# 2back-1motor.net
KiCad netlist of a schematic drawn in EAGLE
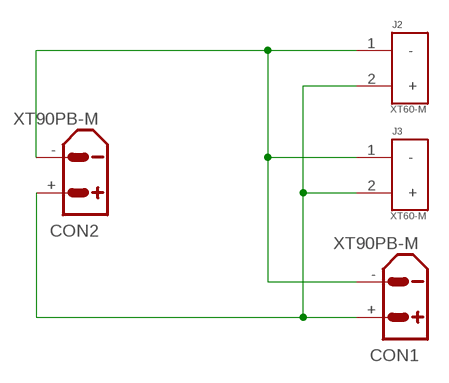
[diagram p0: schematic, sheet 1]

(export (version "E")
  (design (tool "Eeschema 10.0.6"))
  (components
    (comp (ref "CON1")
      (value "XT90PB-M")
      (footprint "eagle-import:XT90PB-M")
      (libsource (lib "eagle-import") (part "XT90PB-M"))
    )
    (comp (ref "CON2")
      (value "XT90PB-M")
      (footprint "eagle-import:XT90PB-M")
      (libsource (lib "eagle-import") (part "XT90PB-M"))
    )
    (comp (ref "J2")
      (value "XT60-M")
      (footprint "eagle-import:AMASS_XT60-M")
      (fields (field (name "MF") "AMASS"))
      (libsource (lib "eagle-import") (part "XT60-M"))
    )
    (comp (ref "J3")
      (value "XT60-M")
      (footprint "eagle-import:AMASS_XT60-M")
      (fields (field (name "MF") "AMASS"))
      (libsource (lib "eagle-import") (part "XT60-M"))
    )
  )
  (nets
    (net (code "1") (name "Net-(J2-+)") (class "Default")
      (node (ref "CON1") (pin "+") (pinfunction "+_+") (pintype "power_in"))
      (node (ref "CON2") (pin "+") (pinfunction "+_+") (pintype "power_in"))
      (node (ref "J2") (pin "2") (pinfunction "+_2") (pintype "passive"))
      (node (ref "J3") (pin "2") (pinfunction "+_2") (pintype "passive"))
    )
    (net (code "2") (name "Net-(J2--)") (class "Default")
      (node (ref "CON1") (pin "-") (pinfunction "-_-") (pintype "power_in"))
      (node (ref "CON2") (pin "-") (pinfunction "-_-") (pintype "power_in"))
      (node (ref "J2") (pin "1") (pinfunction "-_1") (pintype "passive"))
      (node (ref "J3") (pin "1") (pinfunction "-_1") (pintype "passive"))
    )
  )
)
